# POWER.net
KiCad netlist of a schematic drawn in Altium Designer
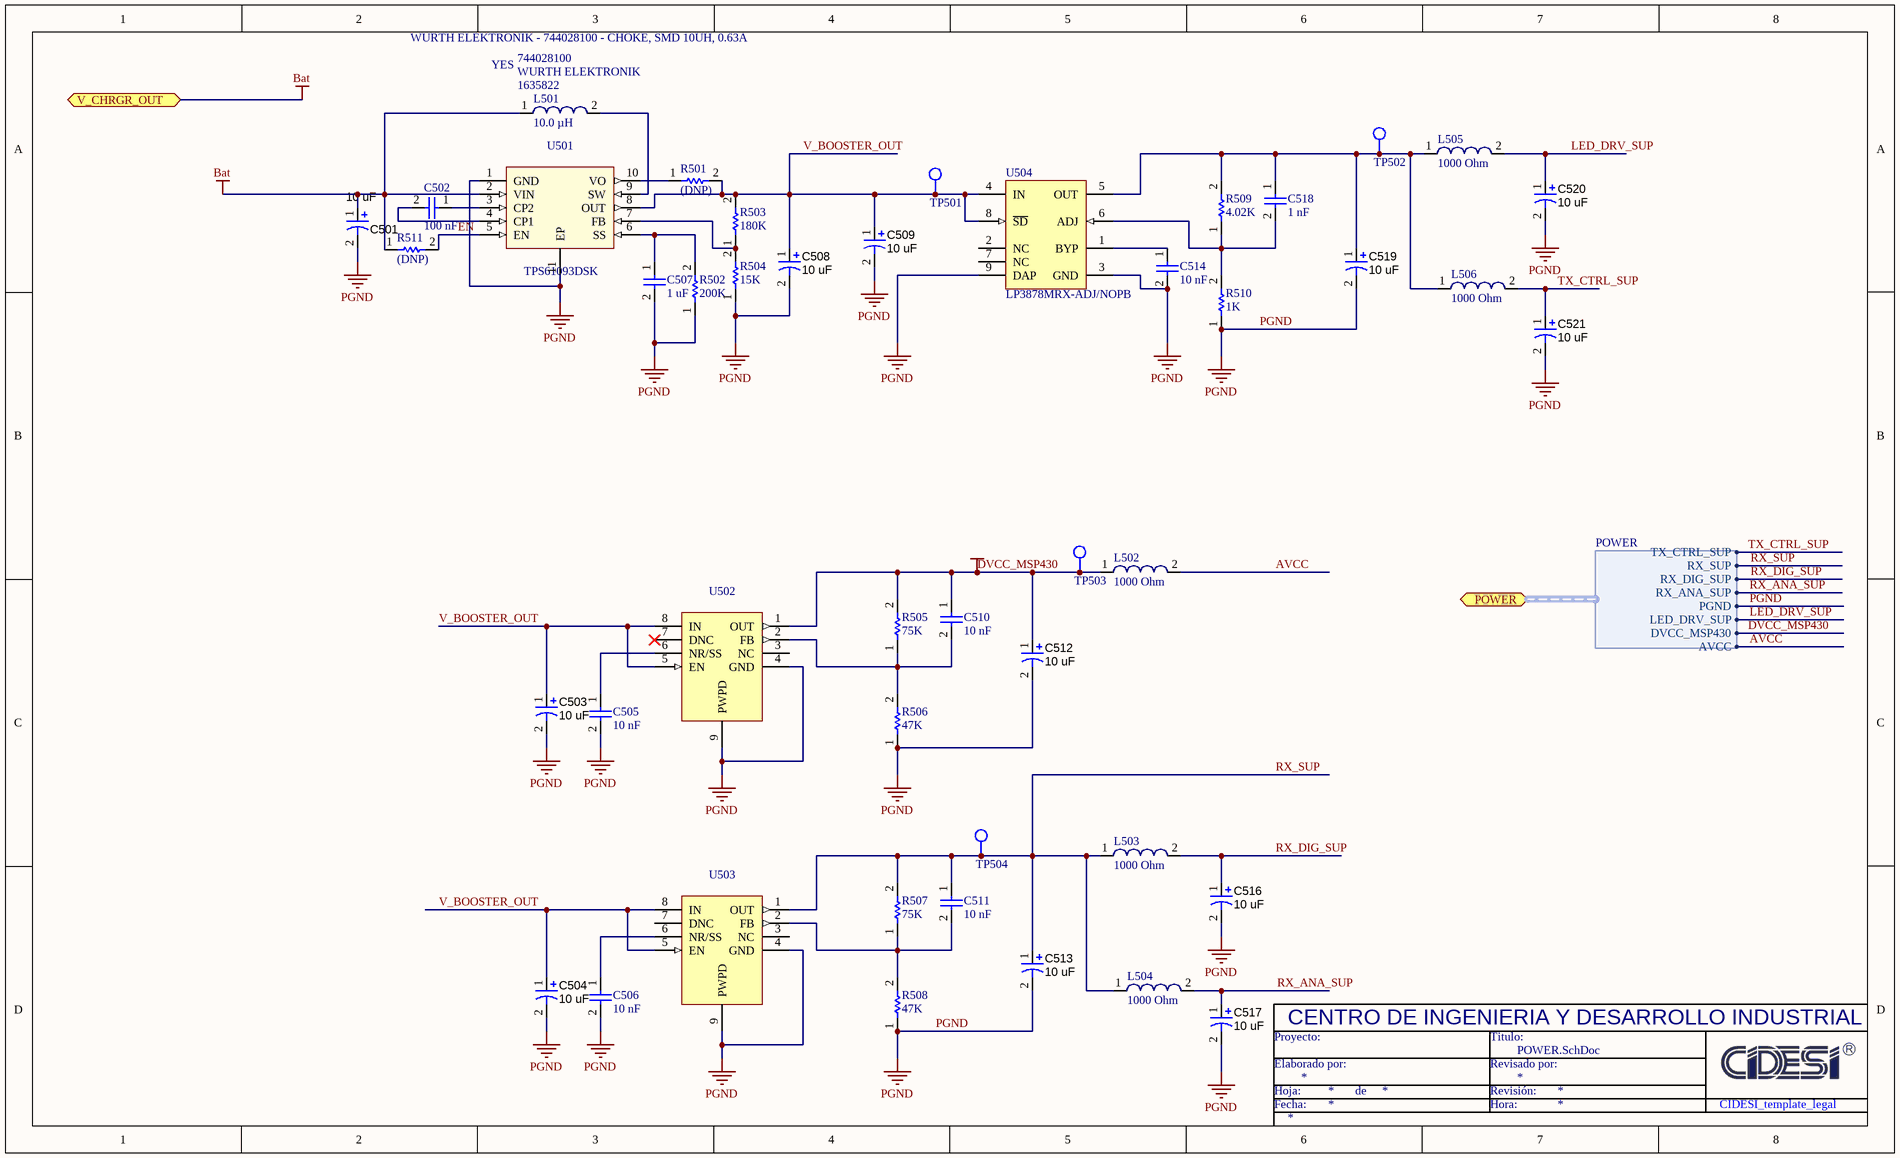
[diagram p0: POWER.SchDoc]

(export (version "E")
  (design (tool "Eeschema 10.0.6"))
  (components
    (comp (ref "C501")
      (value "10 uF")
      (footprint "C0603_P")
      (description "NICHICON - F981A106MMA - CAPACITOR TANT, 10UF, 10V 20%")
      (libsource (lib "TarjetaPrincipalV1_4") (part "F981A106MMA"))
    )
    (comp (ref "C502")
      (value "100 nF")
      (footprint "C0402")
      (description "TDK - C1005X7R1H104M050BB - CAP CERAMIC, 0.1UF, 50V, X7R, 0402")
      (libsource (lib "TarjetaPrincipalV1_4") (part "C1005X7R1H104M050BB"))
    )
    (comp (ref "C503")
      (value "10 uF")
      (footprint "C0603_P")
      (description "NICHICON - F981A106MMA - CAPACITOR TANT, 10UF, 10V 20%")
      (libsource (lib "TarjetaPrincipalV1_4") (part "F981A106MMA"))
    )
    (comp (ref "C504")
      (value "10 uF")
      (footprint "C0603_P")
      (description "NICHICON - F981A106MMA - CAPACITOR TANT, 10UF, 10V 20%")
      (libsource (lib "TarjetaPrincipalV1_4") (part "F981A106MMA"))
    )
    (comp (ref "C505")
      (value "10 nF")
      (footprint "C0402")
      (description "TDK - C1005X7R1H103K050BB - CAP CERAMIC, 0.01UF, 50V, X7R, 0402")
      (libsource (lib "TarjetaPrincipalV1_4") (part "C1005X7R1H103K050BB"))
    )
    (comp (ref "C506")
      (value "10 nF")
      (footprint "C0402")
      (description "TDK - C1005X7R1H103K050BB - CAP CERAMIC, 0.01UF, 50V, X7R, 0402")
      (libsource (lib "TarjetaPrincipalV1_4") (part "C1005X7R1H103K050BB"))
    )
    (comp (ref "C507")
      (value "1 uF")
      (footprint "C0402")
      (description "TDK - C1005X5R1E105K050BC - CAP, MLCC, X5R, 1UF, 25V, 0402")
      (libsource (lib "TarjetaPrincipalV1_4") (part "C1005X5R1E105K050BC"))
    )
    (comp (ref "C508")
      (value "10 uF")
      (footprint "C0603_P")
      (description "NICHICON - F981A106MMA - CAPACITOR TANT, 10UF, 10V 20%")
      (libsource (lib "TarjetaPrincipalV1_4") (part "F981A106MMA"))
    )
    (comp (ref "C509")
      (value "10 uF")
      (footprint "C0603_P")
      (description "NICHICON - F981A106MMA - CAPACITOR TANT, 10UF, 10V 20%")
      (libsource (lib "TarjetaPrincipalV1_4") (part "F981A106MMA"))
    )
    (comp (ref "C510")
      (value "10 nF")
      (footprint "C0402")
      (description "TDK - C1005X7R1H103K050BB - CAP CERAMIC, 0.01UF, 50V, X7R, 0402")
      (libsource (lib "TarjetaPrincipalV1_4") (part "C1005X7R1H103K050BB"))
    )
    (comp (ref "C511")
      (value "10 nF")
      (footprint "C0402")
      (description "TDK - C1005X7R1H103K050BB - CAP CERAMIC, 0.01UF, 50V, X7R, 0402")
      (libsource (lib "TarjetaPrincipalV1_4") (part "C1005X7R1H103K050BB"))
    )
    (comp (ref "C512")
      (value "10 uF")
      (footprint "C0603_P")
      (description "NICHICON - F981A106MMA - CAPACITOR TANT, 10UF, 10V 20%")
      (libsource (lib "TarjetaPrincipalV1_4") (part "F981A106MMA"))
    )
    (comp (ref "C513")
      (value "10 uF")
      (footprint "C0603_P")
      (description "NICHICON - F981A106MMA - CAPACITOR TANT, 10UF, 10V 20%")
      (libsource (lib "TarjetaPrincipalV1_4") (part "F981A106MMA"))
    )
    (comp (ref "C514")
      (value "10 nF")
      (footprint "C0402")
      (description "TDK - C1005X7R1H103K050BB - CAP CERAMIC, 0.01UF, 50V, X7R, 0402")
      (libsource (lib "TarjetaPrincipalV1_4") (part "C1005X7R1H103K050BB"))
    )
    (comp (ref "C516")
      (value "10 uF")
      (footprint "C0603_P")
      (description "NICHICON - F981A106MMA - CAPACITOR TANT, 10UF, 10V 20%")
      (libsource (lib "TarjetaPrincipalV1_4") (part "F981A106MMA"))
    )
    (comp (ref "C517")
      (value "10 uF")
      (footprint "C0603_P")
      (description "NICHICON - F981A106MMA - CAPACITOR TANT, 10UF, 10V 20%")
      (libsource (lib "TarjetaPrincipalV1_4") (part "F981A106MMA"))
    )
    (comp (ref "C518")
      (value "1 nF")
      (footprint "C0402")
      (description "TDK - C1005X7R1E102K050BA - CAPACITOR CERAMIC 1000PF, 25V, X7R, 10%, 0402")
      (libsource (lib "TarjetaPrincipalV1_4") (part "C1005X7R1E102K050BA"))
    )
    (comp (ref "C519")
      (value "10 uF")
      (footprint "C0603_P")
      (description "NICHICON - F981A106MMA - CAPACITOR TANT, 10UF, 10V 20%")
      (libsource (lib "TarjetaPrincipalV1_4") (part "F981A106MMA"))
    )
    (comp (ref "C520")
      (value "10 uF")
      (footprint "C0603_P")
      (description "NICHICON - F981A106MMA - CAPACITOR TANT, 10UF, 10V 20%")
      (libsource (lib "TarjetaPrincipalV1_4") (part "F981A106MMA"))
    )
    (comp (ref "C521")
      (value "10 uF")
      (footprint "C0603_P")
      (description "NICHICON - F981A106MMA - CAPACITOR TANT, 10UF, 10V 20%")
      (libsource (lib "TarjetaPrincipalV1_4") (part "F981A106MMA"))
    )
    (comp (ref "L501")
      (value "10.0 µH")
      (footprint "WE-TPC 2811, T")
      (description "SMD Shielded Tiny Power Inductor WE-TPC, L=10.0 µH")
      (fields
        (field (name "PARTNO") "744028100")
        (field (name "MANUFACTURER") "Würth Elektronik eiSos GmbH")
        (field (name "SUPPLIER PART NUMBER 1") "1635822")
        (field (name "MANUFACTURER 1") "WURTH ELEKTRONIK")
        (field (name "MANUFACTURER PART NUMBER 1") "744028100")
        (field (name "ROHS 1") "YES")
        (field (name "DESCRIPTION 1") "WURTH ELEKTRONIK - 744028100 - CHOKE, SMD 10UH, 0.63A")
        (field (name "CREATED BY") "Christin Zierenner")
      )
      (libsource (lib "TarjetaPrincipalV1_4") (part "WE-TPC 2811, T, 744028100"))
    )
    (comp (ref "L502")
      (value "1000 Ohm")
      (footprint "SMD 0402")
      (description "SMD EMI Suppression Ferrite Beads WE-CBF HF, Z= 1000 Ohm")
      (fields
        (field (name "PARTNO") "742841210")
        (field (name "MANUFACTURER") "Würth Elektronik eiSos GmbH")
        (field (name "CREATED BY") "Christin Zierenner")
      )
      (libsource (lib "TarjetaPrincipalV1_4") (part "WE-CBF HF 0402, 742841210"))
    )
    (comp (ref "L503")
      (value "1000 Ohm")
      (footprint "SMD 0402")
      (description "SMD EMI Suppression Ferrite Beads WE-CBF HF, Z= 1000 Ohm")
      (fields
        (field (name "PARTNO") "742841210")
        (field (name "MANUFACTURER") "Würth Elektronik eiSos GmbH")
        (field (name "CREATED BY") "Christin Zierenner")
      )
      (libsource (lib "TarjetaPrincipalV1_4") (part "WE-CBF HF 0402, 742841210"))
    )
    (comp (ref "L504")
      (value "1000 Ohm")
      (footprint "SMD 0402")
      (description "SMD EMI Suppression Ferrite Beads WE-CBF HF, Z= 1000 Ohm")
      (fields
        (field (name "PARTNO") "742841210")
        (field (name "MANUFACTURER") "Würth Elektronik eiSos GmbH")
        (field (name "CREATED BY") "Christin Zierenner")
      )
      (libsource (lib "TarjetaPrincipalV1_4") (part "WE-CBF HF 0402, 742841210"))
    )
    (comp (ref "L505")
      (value "1000 Ohm")
      (footprint "SMD 0402")
      (description "SMD EMI Suppression Ferrite Beads WE-CBF HF, Z= 1000 Ohm")
      (fields
        (field (name "PARTNO") "742841210")
        (field (name "MANUFACTURER") "Würth Elektronik eiSos GmbH")
        (field (name "CREATED BY") "Christin Zierenner")
      )
      (libsource (lib "TarjetaPrincipalV1_4") (part "WE-CBF HF 0402, 742841210"))
    )
    (comp (ref "L506")
      (value "1000 Ohm")
      (footprint "SMD 0402")
      (description "SMD EMI Suppression Ferrite Beads WE-CBF HF, Z= 1000 Ohm")
      (fields
        (field (name "PARTNO") "742841210")
        (field (name "MANUFACTURER") "Würth Elektronik eiSos GmbH")
        (field (name "CREATED BY") "Christin Zierenner")
      )
      (libsource (lib "TarjetaPrincipalV1_4") (part "WE-CBF HF 0402, 742841210"))
    )
    (comp (ref "R501")
      (value "(DNP)")
      (footprint "0201")
      (description "VISHAY DALE - CRCW02010000Z0ED - RESISTOR, CHIP, JUMPER, ZERO OHM, 50mW, FULL REEL")
      (libsource (lib "TarjetaPrincipalV1_4") (part "CRCW02010000Z0ED"))
    )
    (comp (ref "R502")
      (value "200K")
      (footprint "0201")
      (description "VISHAY DALE - CRCW0201200KFNED - RESISTOR, THICK FILM, 200 KOHM, 50 mW, 1%, FULL REEL")
      (libsource (lib "TarjetaPrincipalV1_4") (part "CRCW0201200KFNED"))
    )
    (comp (ref "R503")
      (value "180K")
      (footprint "0201")
      (description "VISHAY DALE - CRCW0201180KFNED - RESISTOR, THICK FILM, 180 KOHM, 50 mW, 1%, FULL REEL")
      (libsource (lib "TarjetaPrincipalV1_4") (part "CRCW0201180KFNED"))
    )
    (comp (ref "R504")
      (value "15K")
      (footprint "0201")
      (description "VISHAY DALE - CRCW020115K0FNED - RESISTOR, THICK FILM, 15 KOHM, 50 mW, 1%, FULL REEL")
      (libsource (lib "TarjetaPrincipalV1_4") (part "CRCW020115K0FNED"))
    )
    (comp (ref "R505")
      (value "75K")
      (footprint "0201")
      (description "VISHAY DALE - CRCW020175K0FNED - RESISTOR, THICK FILM, 75 KOHM, 50 mW, 1%, FULL REEL")
      (libsource (lib "TarjetaPrincipalV1_4") (part "CRCW020175K0FNED"))
    )
    (comp (ref "R506")
      (value "47K")
      (footprint "0201")
      (description "VISHAY DALE - CRCW020147K0FNED - RESISTOR, THICK FILM, 47 KOHM, 50 mW, 1%, FULL REEL")
      (libsource (lib "TarjetaPrincipalV1_4") (part "CRCW020147K0FNED"))
    )
    (comp (ref "R507")
      (value "75K")
      (footprint "0201")
      (description "VISHAY DALE - CRCW020175K0FNED - RESISTOR, THICK FILM, 75 KOHM, 50 mW, 1%, FULL REEL")
      (libsource (lib "TarjetaPrincipalV1_4") (part "CRCW020175K0FNED"))
    )
    (comp (ref "R508")
      (value "47K")
      (footprint "0201")
      (description "VISHAY DALE - CRCW020147K0FNED - RESISTOR, THICK FILM, 47 KOHM, 50 mW, 1%, FULL REEL")
      (libsource (lib "TarjetaPrincipalV1_4") (part "CRCW020147K0FNED"))
    )
    (comp (ref "R509")
      (value "4.02K")
      (footprint "0201")
      (description "VISHAY DALE - CRCW02014K02FNED - RESISTOR, THICK FILM, 4.02 KOHM, 50 mW, 1%, FULL REEL")
      (libsource (lib "TarjetaPrincipalV1_4") (part "CRCW02014K02FNED"))
    )
    (comp (ref "R510")
      (value "1K")
      (footprint "0201")
      (description "VISHAY DALE - CRCW02011K00FNED - RESISTOR, THICK FILM CHIP, 1KOHM 50mW, 1%, FULL REEL")
      (libsource (lib "TarjetaPrincipalV1_4") (part "CRCW02011K00FNED"))
    )
    (comp (ref "R511")
      (value "(DNP)")
      (footprint "0201")
      (description "VISHAY DALE - CRCW02010000Z0ED - RESISTOR, CHIP, JUMPER, ZERO OHM, 50mW, FULL REEL")
      (libsource (lib "TarjetaPrincipalV1_4") (part "CRCW02010000Z0ED"))
    )
    (comp (ref "TP501")
      (value "Test Point")
      (footprint "TestPoint")
      (libsource (lib "TarjetaPrincipalV1_4") (part "TestPoint"))
    )
    (comp (ref "TP502")
      (value "Test Point")
      (footprint "TestPoint")
      (libsource (lib "TarjetaPrincipalV1_4") (part "TestPoint"))
    )
    (comp (ref "TP503")
      (value "Test Point")
      (footprint "TestPoint")
      (libsource (lib "TarjetaPrincipalV1_4") (part "TestPoint"))
    )
    (comp (ref "TP504")
      (value "Test Point")
      (footprint "TestPoint")
      (libsource (lib "TarjetaPrincipalV1_4") (part "TestPoint"))
    )
    (comp (ref "U501")
      (value "TPS61093DSK")
      (footprint "DSK")
      (description "IC, LOW INPUT BOOST CONVERTER WITH INTEGRATED POWER DIODE AND ISOLATION, SON-10, DSK")
      (fields (field (name "MANUFACTURER") "TEXAS INSTRUMENTS"))
      (libsource (lib "TarjetaPrincipalV1_4") (part "TPS61093DSK"))
    )
    (comp (ref "U502")
      (value "TPS7A4901DGN")
      (footprint "DGN_8P")
      (description "IC, ULTRALOW NOISE, HIGH-PSRR, LDO REGULATOR, VIN 3V TO 35V, 150mA ,MSOP-8, DGN")
      (fields (field (name "MANUFACTURER") "TEXAS INSTRUMENTS"))
      (libsource (lib "TarjetaPrincipalV1_4") (part "TPS7A4901DGN"))
    )
    (comp (ref "U503")
      (value "TPS7A4901DGN")
      (footprint "DGN_8P")
      (description "IC, ULTRALOW NOISE, HIGH-PSRR, LDO REGULATOR, VIN 3V TO 35V, 150mA ,MSOP-8, DGN")
      (fields (field (name "MANUFACTURER") "TEXAS INSTRUMENTS"))
      (libsource (lib "TarjetaPrincipalV1_4") (part "TPS7A4901DGN"))
    )
    (comp (ref "U504")
      (value "LP3878MRX-ADJ/NOPB")
      (footprint "NGT")
      (libsource (lib "TarjetaPrincipalV1_4") (part "LP3878MRX-ADJ/NOPB"))
    )
  )
  (nets
    (net (code "2") (name "/AVCC") (class "Default")
      (node (ref "L502") (pin "2") (pinfunction "2_2") (pintype "passive"))
    )
    (net (code "3") (name "/EN") (class "Default")
      (node (ref "R511") (pin "2") (pinfunction "2_2") (pintype "passive"))
      (node (ref "U501") (pin "5") (pinfunction "EN_5") (pintype "input"))
    )
    (net (code "4") (name "/LED_DRV_SUP") (class "Default")
      (node (ref "C520") (pin "1") (pinfunction "+_1") (pintype "passive"))
      (node (ref "L505") (pin "2") (pinfunction "2_2") (pintype "passive"))
    )
    (net (code "5") (name "/RX_ANA_SUP") (class "Default")
      (node (ref "C517") (pin "1") (pinfunction "+_1") (pintype "passive"))
      (node (ref "L504") (pin "2") (pinfunction "2_2") (pintype "passive"))
    )
    (net (code "6") (name "/RX_DIG_SUP") (class "Default")
      (node (ref "C516") (pin "1") (pinfunction "+_1") (pintype "passive"))
      (node (ref "L503") (pin "2") (pinfunction "2_2") (pintype "passive"))
    )
    (net (code "7") (name "/RX_SUP") (class "Default")
      (node (ref "C511") (pin "1") (pinfunction "1_1") (pintype "passive"))
      (node (ref "C513") (pin "1") (pinfunction "+_1") (pintype "passive"))
      (node (ref "L503") (pin "1") (pinfunction "1_1") (pintype "passive"))
      (node (ref "L504") (pin "1") (pinfunction "1_1") (pintype "passive"))
      (node (ref "R507") (pin "2") (pinfunction "2_2") (pintype "passive"))
      (node (ref "TP504") (pin "1") (pinfunction "1_1") (pintype "passive"))
      (node (ref "U503") (pin "1") (pinfunction "OUT_1") (pintype "output"))
    )
    (net (code "8") (name "/TX_CTRL_SUP") (class "Default")
      (node (ref "C521") (pin "1") (pinfunction "+_1") (pintype "passive"))
      (node (ref "L506") (pin "2") (pinfunction "2_2") (pintype "passive"))
    )
    (net (code "9") (name "/V_BOOSTER_OUT") (class "Default")
      (node (ref "C503") (pin "1") (pinfunction "+_1") (pintype "passive"))
      (node (ref "C504") (pin "1") (pinfunction "+_1") (pintype "passive"))
      (node (ref "C508") (pin "1") (pinfunction "+_1") (pintype "passive"))
      (node (ref "C509") (pin "1") (pinfunction "+_1") (pintype "passive"))
      (node (ref "R501") (pin "2") (pinfunction "2_2") (pintype "passive"))
      (node (ref "R503") (pin "2") (pinfunction "2_2") (pintype "passive"))
      (node (ref "TP501") (pin "1") (pinfunction "1_1") (pintype "passive"))
      (node (ref "U501") (pin "8") (pinfunction "OUT_8") (pintype "output"))
      (node (ref "U502") (pin "5") (pinfunction "EN_5") (pintype "input"))
      (node (ref "U502") (pin "8") (pinfunction "IN_8") (pintype "power_in"))
      (node (ref "U503") (pin "5") (pinfunction "EN_5") (pintype "input"))
      (node (ref "U503") (pin "8") (pinfunction "IN_8") (pintype "power_in"))
      (node (ref "U504") (pin "4") (pinfunction "IN_4") (pintype "power_in"))
      (node (ref "U504") (pin "8") (pinfunction "~{SD}_8") (pintype "input"))
    )
    (net (code "11") (name "Bat") (class "Default")
      (node (ref "C501") (pin "1") (pinfunction "+_1") (pintype "passive"))
      (node (ref "L501") (pin "1") (pinfunction "1_1") (pintype "passive"))
      (node (ref "R511") (pin "1") (pinfunction "1_1") (pintype "passive"))
      (node (ref "U501") (pin "2") (pinfunction "VIN_2") (pintype "input"))
    )
    (net (code "12") (name "DVCC_MSP430") (class "Default")
      (node (ref "C510") (pin "1") (pinfunction "1_1") (pintype "passive"))
      (node (ref "C512") (pin "1") (pinfunction "+_1") (pintype "passive"))
      (node (ref "L502") (pin "1") (pinfunction "1_1") (pintype "passive"))
      (node (ref "R505") (pin "2") (pinfunction "2_2") (pintype "passive"))
      (node (ref "TP503") (pin "1") (pinfunction "1_1") (pintype "passive"))
      (node (ref "U502") (pin "1") (pinfunction "OUT_1") (pintype "output"))
    )
    (net (code "13") (name "Net-(C519-+)") (class "Default")
      (node (ref "C518") (pin "1") (pinfunction "1_1") (pintype "passive"))
      (node (ref "C519") (pin "1") (pinfunction "+_1") (pintype "passive"))
      (node (ref "L505") (pin "1") (pinfunction "1_1") (pintype "passive"))
      (node (ref "L506") (pin "1") (pinfunction "1_1") (pintype "passive"))
      (node (ref "R509") (pin "2") (pinfunction "2_2") (pintype "passive"))
      (node (ref "TP502") (pin "1") (pinfunction "1_1") (pintype "passive"))
      (node (ref "U504") (pin "5") (pinfunction "OUT_5") (pintype "power_in"))
    )
    (net (code "14") (name "Net-(U501-CP1)") (class "Default")
      (node (ref "C502") (pin "2") (pinfunction "2_2") (pintype "passive"))
      (node (ref "U501") (pin "4") (pinfunction "CP1_4") (pintype "input"))
    )
    (net (code "15") (name "Net-(U501-CP2)") (class "Default")
      (node (ref "C502") (pin "1") (pinfunction "1_1") (pintype "passive"))
      (node (ref "U501") (pin "3") (pinfunction "CP2_3") (pintype "input"))
    )
    (net (code "16") (name "Net-(U501-FB)") (class "Default")
      (node (ref "R503") (pin "1") (pinfunction "1_1") (pintype "passive"))
      (node (ref "R504") (pin "2") (pinfunction "2_2") (pintype "passive"))
      (node (ref "U501") (pin "7") (pinfunction "FB_7") (pintype "input"))
    )
    (net (code "17") (name "Net-(U501-SS)") (class "Default")
      (node (ref "C507") (pin "1") (pinfunction "1_1") (pintype "passive"))
      (node (ref "R502") (pin "2") (pinfunction "2_2") (pintype "passive"))
      (node (ref "U501") (pin "6") (pinfunction "SS_6") (pintype "input"))
    )
    (net (code "18") (name "Net-(U501-SW)") (class "Default")
      (node (ref "L501") (pin "2") (pinfunction "2_2") (pintype "passive"))
      (node (ref "U501") (pin "9") (pinfunction "SW_9") (pintype "input"))
    )
    (net (code "19") (name "Net-(U501-VO)") (class "Default")
      (node (ref "R501") (pin "1") (pinfunction "1_1") (pintype "passive"))
      (node (ref "U501") (pin "10") (pinfunction "VO_10") (pintype "output"))
    )
    (net (code "20") (name "Net-(U502-FB)") (class "Default")
      (node (ref "C510") (pin "2") (pinfunction "2_2") (pintype "passive"))
      (node (ref "R505") (pin "1") (pinfunction "1_1") (pintype "passive"))
      (node (ref "R506") (pin "2") (pinfunction "2_2") (pintype "passive"))
      (node (ref "U502") (pin "2") (pinfunction "FB_2") (pintype "output"))
    )
    (net (code "21") (name "Net-(U502-NR{slash}SS)") (class "Default")
      (node (ref "C505") (pin "1") (pinfunction "1_1") (pintype "passive"))
      (node (ref "U502") (pin "6") (pinfunction "NR/SS_6") (pintype "passive"))
    )
    (net (code "22") (name "Net-(U503-FB)") (class "Default")
      (node (ref "C511") (pin "2") (pinfunction "2_2") (pintype "passive"))
      (node (ref "R507") (pin "1") (pinfunction "1_1") (pintype "passive"))
      (node (ref "R508") (pin "2") (pinfunction "2_2") (pintype "passive"))
      (node (ref "U503") (pin "2") (pinfunction "FB_2") (pintype "output"))
    )
    (net (code "23") (name "Net-(U503-NR{slash}SS)") (class "Default")
      (node (ref "C506") (pin "1") (pinfunction "1_1") (pintype "passive"))
      (node (ref "U503") (pin "6") (pinfunction "NR/SS_6") (pintype "passive"))
    )
    (net (code "24") (name "Net-(U504-ADJ)") (class "Default")
      (node (ref "C518") (pin "2") (pinfunction "2_2") (pintype "passive"))
      (node (ref "R509") (pin "1") (pinfunction "1_1") (pintype "passive"))
      (node (ref "R510") (pin "2") (pinfunction "2_2") (pintype "passive"))
      (node (ref "U504") (pin "6") (pinfunction "ADJ_6") (pintype "input"))
    )
    (net (code "25") (name "Net-(U504-BYP)") (class "Default")
      (node (ref "C514") (pin "1") (pinfunction "1_1") (pintype "passive"))
      (node (ref "U504") (pin "1") (pinfunction "BYP_1") (pintype "passive"))
    )
    (net (code "26") (name "PGND") (class "Default")
      (node (ref "C501") (pin "2") (pinfunction "-_2") (pintype "passive"))
      (node (ref "C503") (pin "2") (pinfunction "-_2") (pintype "passive"))
      (node (ref "C504") (pin "2") (pinfunction "-_2") (pintype "passive"))
      (node (ref "C505") (pin "2") (pinfunction "2_2") (pintype "passive"))
      (node (ref "C506") (pin "2") (pinfunction "2_2") (pintype "passive"))
      (node (ref "C507") (pin "2") (pinfunction "2_2") (pintype "passive"))
      (node (ref "C508") (pin "2") (pinfunction "-_2") (pintype "passive"))
      (node (ref "C509") (pin "2") (pinfunction "-_2") (pintype "passive"))
      (node (ref "C512") (pin "2") (pinfunction "-_2") (pintype "passive"))
      (node (ref "C513") (pin "2") (pinfunction "-_2") (pintype "passive"))
      (node (ref "C514") (pin "2") (pinfunction "2_2") (pintype "passive"))
      (node (ref "C516") (pin "2") (pinfunction "-_2") (pintype "passive"))
      (node (ref "C517") (pin "2") (pinfunction "-_2") (pintype "passive"))
      (node (ref "C519") (pin "2") (pinfunction "-_2") (pintype "passive"))
      (node (ref "C520") (pin "2") (pinfunction "-_2") (pintype "passive"))
      (node (ref "C521") (pin "2") (pinfunction "-_2") (pintype "passive"))
      (node (ref "R502") (pin "1") (pinfunction "1_1") (pintype "passive"))
      (node (ref "R504") (pin "1") (pinfunction "1_1") (pintype "passive"))
      (node (ref "R506") (pin "1") (pinfunction "1_1") (pintype "passive"))
      (node (ref "R508") (pin "1") (pinfunction "1_1") (pintype "passive"))
      (node (ref "R510") (pin "1") (pinfunction "1_1") (pintype "passive"))
      (node (ref "U501") (pin "1") (pinfunction "GND_1") (pintype "power_in"))
      (node (ref "U501") (pin "11") (pinfunction "EP_11") (pintype "power_in"))
      (node (ref "U502") (pin "4") (pinfunction "GND_4") (pintype "power_in"))
      (node (ref "U502") (pin "9") (pinfunction "PWPD_9") (pintype "power_in"))
      (node (ref "U503") (pin "4") (pinfunction "GND_4") (pintype "power_in"))
      (node (ref "U503") (pin "9") (pinfunction "PWPD_9") (pintype "power_in"))
      (node (ref "U504") (pin "3") (pinfunction "GND_3") (pintype "power_in"))
      (node (ref "U504") (pin "9") (pinfunction "DAP_9") (pintype "power_in"))
    )
    (net (code "27") (name "unconnected-(U502-DNC-Pad7)") (class "Default")
      (node (ref "U502") (pin "7") (pinfunction "DNC_7") (pintype "passive+no_connect"))
    )
    (net (code "28") (name "unconnected-(U502-NC-Pad3)") (class "Default")
      (node (ref "U502") (pin "3") (pinfunction "NC_3") (pintype "passive"))
    )
    (net (code "29") (name "unconnected-(U503-DNC-Pad7)") (class "Default")
      (node (ref "U503") (pin "7") (pinfunction "DNC_7") (pintype "passive"))
    )
    (net (code "30") (name "unconnected-(U503-NC-Pad3)") (class "Default")
      (node (ref "U503") (pin "3") (pinfunction "NC_3") (pintype "passive"))
    )
    (net (code "31") (name "unconnected-(U504-NC-Pad2)") (class "Default")
      (node (ref "U504") (pin "2") (pinfunction "NC_2") (pintype "passive"))
    )
    (net (code "32") (name "unconnected-(U504-NC-Pad7)") (class "Default")
      (node (ref "U504") (pin "7") (pinfunction "NC_7") (pintype "passive"))
    )
  )
)
